# CTR-Lower-Main-Board-Rev-A-Sensors-4.net
KiCad netlist of a schematic drawn in Altium Designer
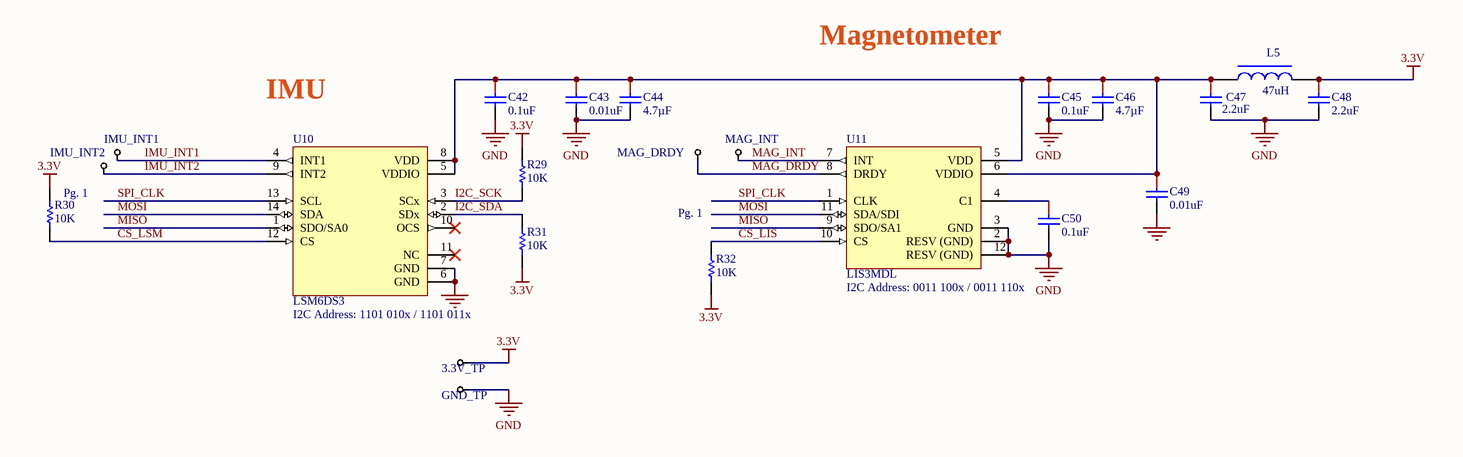
[diagram p0: CTR-Lower-Main-Board-Rev-A-Sensors-4.SchDoc]

(export (version "E")
  (design (tool "Eeschema 10.0.6"))
  (components
    (comp (ref "3.3V_TP")
      (value "3V")
      (footprint "TestPoint-TH 35 mil")
      (description "Test Point")
      (libsource (lib "OLogic-Misc") (part "TestPoint, small"))
    )
    (comp (ref "C42")
      (value "0.1uF")
      (footprint "CAPC0402(1005)_N")
      (description "0.1uF 0402 50V")
      (fields
        (field (name "MANUFACTURER") "TDK Corporation")
        (field (name "MANUFACTURER PART NUMBER") "CGA2B3X7R1H104K050BB")
        (field (name "CREATOR") "osman")
      )
      (libsource (lib "OLogic-Passive") (part "CAP CER 0.1UF 50V 10% X7R 0402"))
    )
    (comp (ref "C43")
      (value "0.01uF")
      (footprint "CAPC0402(1005)_N")
      (description "0.01uF 0402")
      (fields
        (field (name "MANUFACTURER") "Murata Electronics North America")
        (field (name "MANUFACTURER PART NUMBER") "GRM155R71E103KA01D")
      )
      (libsource (lib "OLogic-Passive") (part "CAP CER 0.01UF 25V 10% X5R 0402"))
    )
    (comp (ref "C44")
      (value "4.7UF 0603")
      (footprint "CAPC0603(1608)_L")
      (fields
        (field (name "MANUFACTURER") "Taiyo Yuden")
        (field (name "MANUFACTURER PART NUMBER") "EMK107ABJ475KA-T")
        (field (name "TOLERANCE") "±10%")
        (field (name "CAPACITANCE") "4.7µF")
        (field (name "CREATOR") "osman")
      )
      (libsource (lib "OLogic-Passive") (part "CAP CER 4.7UF 16V 10% X5R 0603"))
    )
    (comp (ref "C45")
      (value "0.1uF")
      (footprint "CAPC0402(1005)_N")
      (description "0.1uF 0402 50V")
      (fields
        (field (name "MANUFACTURER") "TDK Corporation")
        (field (name "MANUFACTURER PART NUMBER") "CGA2B3X7R1H104K050BB")
        (field (name "CREATOR") "osman")
      )
      (libsource (lib "OLogic-Passive") (part "CAP CER 0.1UF 50V 10% X7R 0402"))
    )
    (comp (ref "C46")
      (value "4.7UF 0603")
      (footprint "CAPC0603(1608)_L")
      (fields
        (field (name "MANUFACTURER") "Taiyo Yuden")
        (field (name "MANUFACTURER PART NUMBER") "EMK107ABJ475KA-T")
        (field (name "TOLERANCE") "±10%")
        (field (name "CAPACITANCE") "4.7µF")
        (field (name "CREATOR") "osman")
      )
      (libsource (lib "OLogic-Passive") (part "CAP CER 4.7UF 16V 10% X5R 0603"))
    )
    (comp (ref "C47")
      (value "2.2uF")
      (footprint "CAPC0402(1005)_N")
      (description "2.2uF 0402")
      (fields
        (field (name "MANUFACTURER") "TDK Corporation")
        (field (name "MANUFACTURER PART NUMBER") "C1005X5R1V225K050BC")
        (field (name "CREATOR") "osman")
      )
      (libsource (lib "OLogic-Passive") (part "CAP CER 2.2UF 35V 10% X5R 0402"))
    )
    (comp (ref "C48")
      (value "2.2uF")
      (footprint "CAPC0402(1005)_N")
      (description "2.2uF 0402")
      (fields
        (field (name "MANUFACTURER") "TDK Corporation")
        (field (name "MANUFACTURER PART NUMBER") "C1005X5R1V225K050BC")
        (field (name "CREATOR") "osman")
      )
      (libsource (lib "OLogic-Passive") (part "CAP CER 2.2UF 35V 10% X5R 0402"))
    )
    (comp (ref "C49")
      (value "0.01uF")
      (footprint "CAPC0402(1005)_N")
      (description "0.01uF 0402")
      (fields
        (field (name "MANUFACTURER") "Murata Electronics North America")
        (field (name "MANUFACTURER PART NUMBER") "GRM155R71E103KA01D")
      )
      (libsource (lib "OLogic-Passive") (part "CAP CER 0.01UF 25V 10% X5R 0402"))
    )
    (comp (ref "C50")
      (value "0.1uF")
      (footprint "CAPC0402(1005)_N")
      (description "0.1uF 0402 50V")
      (fields
        (field (name "MANUFACTURER") "TDK Corporation")
        (field (name "MANUFACTURER PART NUMBER") "CGA2B3X7R1H104K050BB")
        (field (name "CREATOR") "osman")
      )
      (libsource (lib "OLogic-Passive") (part "CAP CER 0.1UF 50V 10% X7R 0402"))
    )
    (comp (ref "GND_TP")
      (value "GND")
      (footprint "TestPoint-TH 35 mil")
      (description "Test Point")
      (libsource (lib "OLogic-Misc") (part "TestPoint, small"))
    )
    (comp (ref "IMU_INT1")
      (value "Test Point")
      (footprint "TestPoint-TH 42 mil")
      (libsource (lib "OLogic-Misc") (part "TestPoint, small"))
    )
    (comp (ref "IMU_INT2")
      (value "Test Point")
      (footprint "TestPoint-TH 42 mil")
      (libsource (lib "OLogic-Misc") (part "TestPoint, small"))
    )
    (comp (ref "L5")
      (value "47uH")
      (footprint "IND-2012 Chip")
      (description "47uH 0805")
      (fields
        (field (name "MANUFACTURER") "TDK Corporation")
        (field (name "MANUFACTURER PART NUMBER") "MLZ2012M470WT000")
      )
      (libsource (lib "OLogic-Passive") (part "INDUCTOR MULTILAYER 47UH 100mA 0805"))
    )
    (comp (ref "MAG_DRDY")
      (value "Test Point")
      (footprint "TestPoint-TH 42 mil")
      (libsource (lib "OLogic-Misc") (part "TestPoint, small"))
    )
    (comp (ref "MAG_INT")
      (value "Test Point")
      (footprint "TestPoint-TH 42 mil")
      (libsource (lib "OLogic-Misc") (part "TestPoint, small"))
    )
    (comp (ref "R29")
      (value "10K")
      (footprint "RESC0402(1005)_N")
      (description "10K 0402")
      (fields
        (field (name "MANUFACTURER") "Panasonic Electronic Components")
        (field (name "MANUFACTURER PART NUMBER") "ERJ-2GEJ103X")
        (field (name "CREATOR") "ted")
      )
      (libsource (lib "OLogic-Passive") (part "RES 10K OHM 5% 1/10W 0402"))
    )
    (comp (ref "R30")
      (value "10K")
      (footprint "RESC0402(1005)_N")
      (description "10K 0402")
      (fields
        (field (name "MANUFACTURER") "Panasonic Electronic Components")
        (field (name "MANUFACTURER PART NUMBER") "ERJ-2GEJ103X")
        (field (name "CREATOR") "ted")
      )
      (libsource (lib "OLogic-Passive") (part "RES 10K OHM 5% 1/10W 0402"))
    )
    (comp (ref "R31")
      (value "10K")
      (footprint "RESC0402(1005)_N")
      (description "10K 0402")
      (fields
        (field (name "MANUFACTURER") "Panasonic Electronic Components")
        (field (name "MANUFACTURER PART NUMBER") "ERJ-2GEJ103X")
        (field (name "CREATOR") "ted")
      )
      (libsource (lib "OLogic-Passive") (part "RES 10K OHM 5% 1/10W 0402"))
    )
    (comp (ref "R32")
      (value "10K")
      (footprint "RESC0402(1005)_N")
      (description "10K 0402")
      (fields
        (field (name "MANUFACTURER") "Panasonic Electronic Components")
        (field (name "MANUFACTURER PART NUMBER") "ERJ-2GEJ103X")
        (field (name "CREATOR") "ted")
      )
      (libsource (lib "OLogic-Passive") (part "RES 10K OHM 5% 1/10W 0402"))
    )
    (comp (ref "U10")
      (value "LSM6DS3")
      (footprint "LSM6DS3")
      (description "3D ACC/GYRO INEMO 14VFLGA")
      (fields
        (field (name "MANUFACTURER") "STMicroelectronics")
        (field (name "MANUFACTURER PART NUMBER") "LSM6DS3")
        (field (name "I2C ADDRESS") "1101 010x / 1101 011x")
        (field (name "CREATOR") "osman")
      )
      (libsource (lib "OLogic-Sensors") (part "LSM6DS3"))
    )
    (comp (ref "U11")
      (value "LIS3MDL")
      (footprint "LIS3MDL")
      (description "IC MAGNETOMETER 3-AXIS 12LGA")
      (fields
        (field (name "MANUFACTURER") "STMicroelectronics")
        (field (name "MANUFACTURER PART NUMBER") "LIS3MDL")
        (field (name "I2C ADDRESS") "0011 100x / 0011 110x")
        (field (name "CREATOR") "osman")
      )
      (libsource (lib "OLogic-Sensors") (part "LIS3MDL"))
    )
  )
  (nets
    (net (code "1") (name "/CS_LIS") (class "Default")
      (node (ref "R32") (pin "2") (pinfunction "2_2") (pintype "passive"))
      (node (ref "U11") (pin "10") (pinfunction "CS_10") (pintype "input"))
    )
    (net (code "2") (name "/CS_LSM") (class "Default")
      (node (ref "R30") (pin "1") (pinfunction "1_1") (pintype "passive"))
      (node (ref "U10") (pin "12") (pinfunction "CS_12") (pintype "input"))
    )
    (net (code "3") (name "/I2C_SCK") (class "Default")
      (node (ref "R29") (pin "1") (pinfunction "1_1") (pintype "passive"))
      (node (ref "U10") (pin "3") (pinfunction "SCx_3") (pintype "input"))
    )
    (net (code "4") (name "/I2C_SDA") (class "Default")
      (node (ref "R31") (pin "2") (pinfunction "2_2") (pintype "passive"))
      (node (ref "U10") (pin "2") (pinfunction "SDx_2") (pintype "bidirectional"))
    )
    (net (code "5") (name "/IMU_INT1") (class "Default")
      (node (ref "IMU_INT1") (pin "1") (pinfunction "1_1") (pintype "passive"))
      (node (ref "U10") (pin "4") (pinfunction "INT1_4") (pintype "output"))
    )
    (net (code "6") (name "/IMU_INT2") (class "Default")
      (node (ref "IMU_INT2") (pin "1") (pinfunction "1_1") (pintype "passive"))
      (node (ref "U10") (pin "9") (pinfunction "INT2_9") (pintype "output"))
    )
    (net (code "7") (name "/MAG_DRDY") (class "Default")
      (node (ref "MAG_DRDY") (pin "1") (pinfunction "1_1") (pintype "passive"))
      (node (ref "U11") (pin "8") (pinfunction "DRDY_8") (pintype "output"))
    )
    (net (code "8") (name "/MAG_INT") (class "Default")
      (node (ref "MAG_INT") (pin "1") (pinfunction "1_1") (pintype "passive"))
      (node (ref "U11") (pin "7") (pinfunction "INT_7") (pintype "output"))
    )
    (net (code "9") (name "/MISO") (class "Default")
      (node (ref "U10") (pin "1") (pinfunction "SDO/SA0_1") (pintype "bidirectional"))
      (node (ref "U11") (pin "9") (pinfunction "SDO/SA1_9") (pintype "bidirectional"))
    )
    (net (code "10") (name "/MOSI") (class "Default")
      (node (ref "U10") (pin "14") (pinfunction "SDA_14") (pintype "bidirectional"))
      (node (ref "U11") (pin "11") (pinfunction "SDA/SDI_11") (pintype "bidirectional"))
    )
    (net (code "11") (name "/SPI_CLK") (class "Default")
      (node (ref "U10") (pin "13") (pinfunction "SCL_13") (pintype "input"))
      (node (ref "U11") (pin "1") (pinfunction "CLK_1") (pintype "input"))
    )
    (net (code "12") (name "3.3V") (class "Default")
      (node (ref "3.3V_TP") (pin "1") (pinfunction "1_1") (pintype "passive"))
      (node (ref "C48") (pin "1") (pinfunction "1_1") (pintype "passive"))
      (node (ref "L5") (pin "2") (pinfunction "2_2") (pintype "passive"))
      (node (ref "R29") (pin "2") (pinfunction "2_2") (pintype "passive"))
      (node (ref "R30") (pin "2") (pinfunction "2_2") (pintype "passive"))
      (node (ref "R31") (pin "1") (pinfunction "1_1") (pintype "passive"))
      (node (ref "R32") (pin "1") (pinfunction "1_1") (pintype "passive"))
    )
    (net (code "13") (name "GND") (class "Default")
      (node (ref "C42") (pin "2") (pinfunction "2_2") (pintype "passive"))
      (node (ref "C43") (pin "2") (pinfunction "2_2") (pintype "passive"))
      (node (ref "C44") (pin "2") (pinfunction "2_2") (pintype "passive"))
      (node (ref "C45") (pin "2") (pinfunction "2_2") (pintype "passive"))
      (node (ref "C46") (pin "2") (pinfunction "2_2") (pintype "passive"))
      (node (ref "C47") (pin "2") (pinfunction "2_2") (pintype "passive"))
      (node (ref "C48") (pin "2") (pinfunction "2_2") (pintype "passive"))
      (node (ref "C49") (pin "2") (pinfunction "2_2") (pintype "passive"))
      (node (ref "C50") (pin "2") (pinfunction "2_2") (pintype "passive"))
      (node (ref "GND_TP") (pin "1") (pinfunction "1_1") (pintype "passive"))
      (node (ref "U10") (pin "6") (pinfunction "GND_6") (pintype "power_in"))
      (node (ref "U10") (pin "7") (pinfunction "GND_7") (pintype "power_in"))
      (node (ref "U11") (pin "12") (pinfunction "RESV_(GND)_12") (pintype "power_in"))
      (node (ref "U11") (pin "2") (pinfunction "RESV_(GND)_2") (pintype "power_in"))
      (node (ref "U11") (pin "3") (pinfunction "GND_3") (pintype "power_in"))
    )
    (net (code "14") (name "Net-(U10-VDD)") (class "Default")
      (node (ref "C42") (pin "1") (pinfunction "1_1") (pintype "passive"))
      (node (ref "C43") (pin "1") (pinfunction "1_1") (pintype "passive"))
      (node (ref "C44") (pin "1") (pinfunction "1_1") (pintype "passive"))
      (node (ref "C45") (pin "1") (pinfunction "1_1") (pintype "passive"))
      (node (ref "C46") (pin "1") (pinfunction "1_1") (pintype "passive"))
      (node (ref "C47") (pin "1") (pinfunction "1_1") (pintype "passive"))
      (node (ref "C49") (pin "1") (pinfunction "1_1") (pintype "passive"))
      (node (ref "L5") (pin "1") (pinfunction "1_1") (pintype "passive"))
      (node (ref "U10") (pin "5") (pinfunction "VDDIO_5") (pintype "power_in"))
      (node (ref "U10") (pin "8") (pinfunction "VDD_8") (pintype "power_in"))
      (node (ref "U11") (pin "5") (pinfunction "VDD_5") (pintype "power_in"))
      (node (ref "U11") (pin "6") (pinfunction "VDDIO_6") (pintype "power_in"))
    )
    (net (code "15") (name "Net-(U11-C1)") (class "Default")
      (node (ref "C50") (pin "1") (pinfunction "1_1") (pintype "passive"))
      (node (ref "U11") (pin "4") (pinfunction "C1_4") (pintype "power_in"))
    )
    (net (code "16") (name "unconnected-(U10-NC-Pad11)") (class "Default")
      (node (ref "U10") (pin "11") (pinfunction "NC_11") (pintype "passive+no_connect"))
    )
    (net (code "17") (name "unconnected-(U10-OCS-Pad10)") (class "Default")
      (node (ref "U10") (pin "10") (pinfunction "OCS_10") (pintype "output+no_connect"))
    )
  )
)
